# PoE.net
KiCad netlist of a schematic drawn in Altium Designer
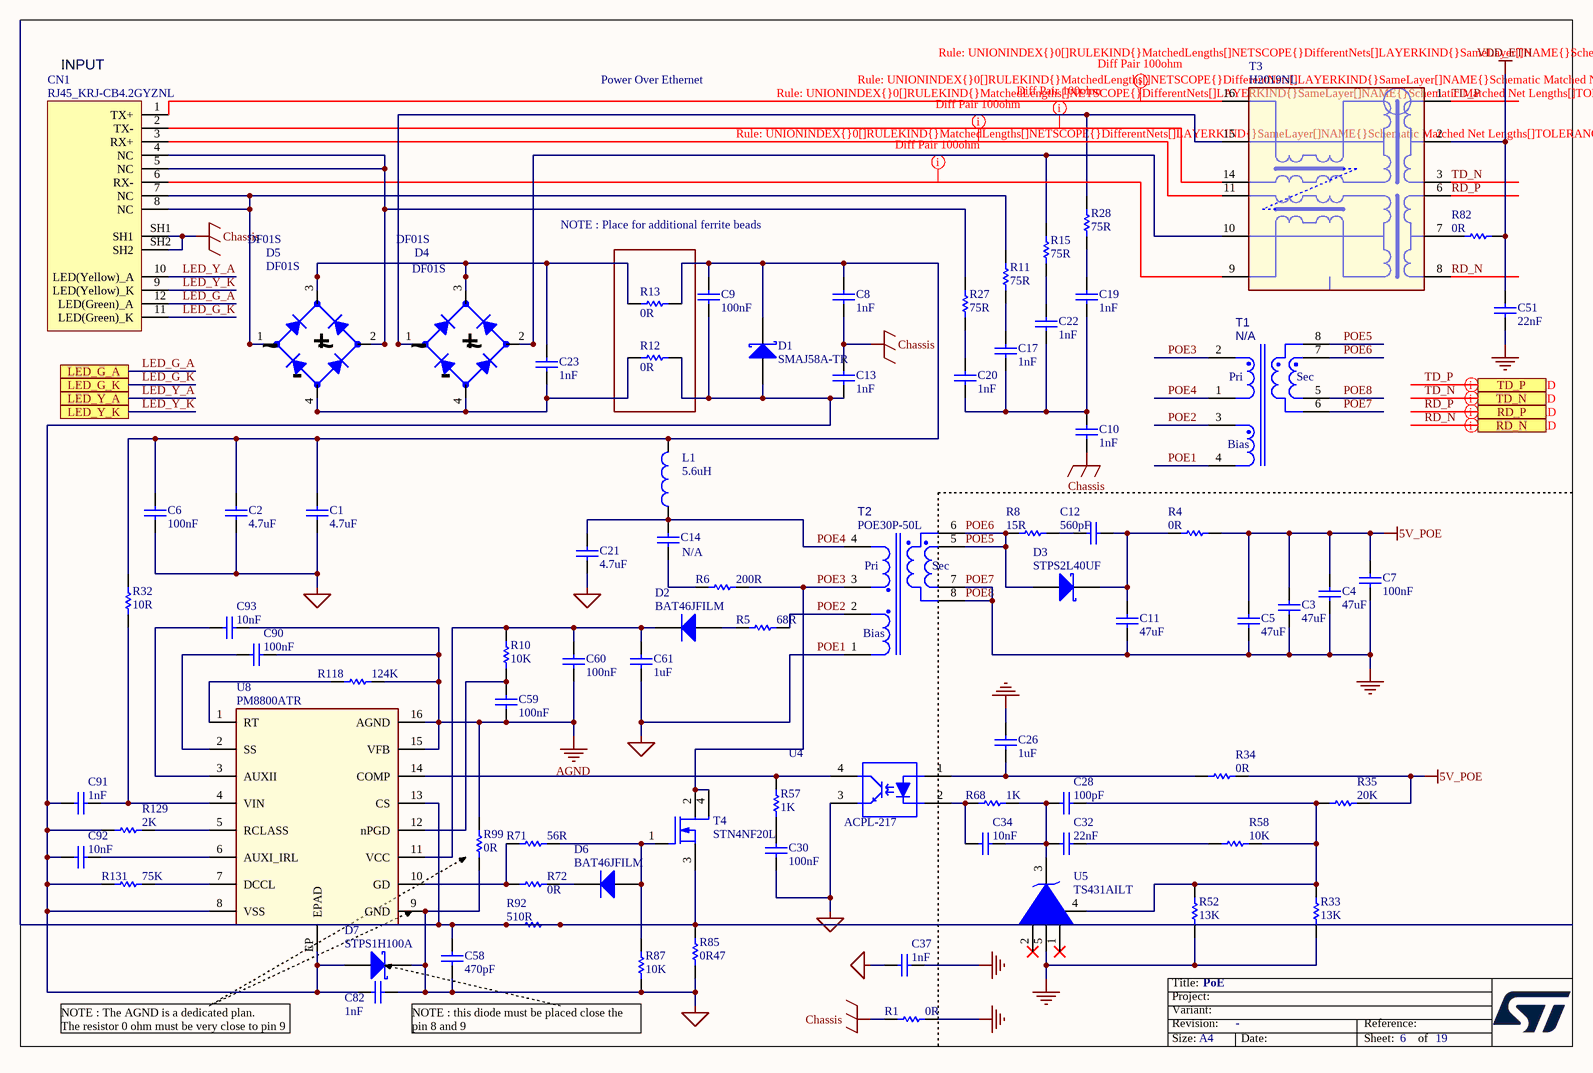
[diagram p0: PoE.SchDoc]

(export (version "E")
  (design (tool "Eeschema 10.0.6"))
  (components
    (comp (ref "C1")
      (value "4.7uF")
      (footprint "C1210")
      (description "Capacitor, MLCC, 4.7uF, 100V, X7S, +/-10%, 1210, T=2mm")
      (fields
        (field (name "INTERNAL_PART_NUMBER") "MCD-02212")
        (field (name "MANUFACTURER_PART_NUMBER") "CGA6M3X7S2A475K200AB")
      )
      (libsource (lib "MCD_PARTS_database") (part "Capacitor"))
    )
    (comp (ref "C2")
      (value "4.7uF")
      (footprint "C1210")
      (description "Capacitor, MLCC, 4.7uF, 100V, X7S, +/-10%, 1210, T=2mm")
      (fields
        (field (name "INTERNAL_PART_NUMBER") "MCD-02212")
        (field (name "MANUFACTURER_PART_NUMBER") "CGA6M3X7S2A475K200AB")
      )
      (libsource (lib "MCD_PARTS_database") (part "Capacitor"))
    )
    (comp (ref "C3")
      (value "47uF")
      (footprint "C0805")
      (description "Capacitor, MLCC, 47uF, 10V, X5R, 20%, 0805, T=1,25mm")
      (fields
        (field (name "INTERNAL_PART_NUMBER") "MCD-00204")
        (field (name "MANUFACTURER_PART_NUMBER") "GRM21BR61A476ME15K")
        (field (name "PROVIDED_BY") "Subcon")
      )
      (libsource (lib "MCD_PARTS_database") (part "Capacitor"))
    )
    (comp (ref "C4")
      (value "47uF")
      (footprint "C0805")
      (description "Capacitor, MLCC, 47uF, 10V, X5R, 20%, 0805, T=1,25mm")
      (fields
        (field (name "INTERNAL_PART_NUMBER") "MCD-00204")
        (field (name "MANUFACTURER_PART_NUMBER") "GRM21BR61A476ME15K")
        (field (name "PROVIDED_BY") "Subcon")
      )
      (libsource (lib "MCD_PARTS_database") (part "Capacitor"))
    )
    (comp (ref "C5")
      (value "47uF")
      (footprint "C0805")
      (description "Capacitor, MLCC, 47uF, 10V, X5R, 20%, 0805, T=1,25mm")
      (fields
        (field (name "INTERNAL_PART_NUMBER") "MCD-00204")
        (field (name "MANUFACTURER_PART_NUMBER") "GRM21BR61A476ME15K")
        (field (name "PROVIDED_BY") "Subcon")
      )
      (libsource (lib "MCD_PARTS_database") (part "Capacitor"))
    )
    (comp (ref "C6")
      (value "100nF")
      (footprint "C0805")
      (description "Capacitor,100nF,100V,X7R,10%,0805")
      (fields
        (field (name "INTERNAL_PART_NUMBER") "MCD-01093")
        (field (name "MANUFACTURER_PART_NUMBER") "C2012X7R2A104K125AA")
        (field (name "PROVIDED_BY") "Subcon")
      )
      (libsource (lib "MCD_PARTS_database") (part "Capacitor"))
    )
    (comp (ref "C7")
      (value "100nF")
      (footprint "C0603")
      (description "Capacitor, MLCC, 100nF, 16V, X7R, 10%, 0603, T=0,8mm")
      (fields
        (field (name "INTERNAL_PART_NUMBER") "MCD-00211")
        (field (name "MANUFACTURER_PART_NUMBER") "CC0603KRX7R7BB104")
        (field (name "PROVIDED_BY") "Subcon")
      )
      (libsource (lib "MCD_PARTS_database") (part "Capacitor"))
    )
    (comp (ref "C8")
      (value "1nF")
      (footprint "C0603")
      (description "Capacitor,1nF,100V,X7R,10%,0603")
      (fields
        (field (name "INTERNAL_PART_NUMBER") "MCD-01091")
        (field (name "MANUFACTURER_PART_NUMBER") "CC0603KRX7R0BB102")
        (field (name "PROVIDED_BY") "Subcon")
      )
      (libsource (lib "MCD_PARTS_database") (part "Capacitor"))
    )
    (comp (ref "C9")
      (value "100nF")
      (footprint "C0805")
      (description "Capacitor,100nF,100V,X7R,10%,0805")
      (fields
        (field (name "INTERNAL_PART_NUMBER") "MCD-01093")
        (field (name "MANUFACTURER_PART_NUMBER") "C2012X7R2A104K125AA")
        (field (name "PROVIDED_BY") "Subcon")
      )
      (libsource (lib "MCD_PARTS_database") (part "Capacitor"))
    )
    (comp (ref "C10")
      (value "1nF")
      (footprint "C1206_H1P6")
      (description "Capacitor, MLCC, 1nF, 2KV, X7R, 10%, 1206, T=1,25mm")
      (fields
        (field (name "INTERNAL_PART_NUMBER") "MCD-00722")
        (field (name "MANUFACTURER_PART_NUMBER") "CC1206KKX7RDBB102")
        (field (name "PROVIDED_BY") "Subcon")
      )
      (libsource (lib "MCD_PARTS_database") (part "Capacitor"))
    )
    (comp (ref "C11")
      (value "47uF")
      (footprint "C0805")
      (description "Capacitor, MLCC, 47uF, 10V, X5R, 20%, 0805, T=1,25mm")
      (fields
        (field (name "INTERNAL_PART_NUMBER") "MCD-00204")
        (field (name "MANUFACTURER_PART_NUMBER") "GRM21BR61A476ME15K")
        (field (name "PROVIDED_BY") "Subcon")
      )
      (libsource (lib "MCD_PARTS_database") (part "Capacitor"))
    )
    (comp (ref "C12")
      (value "560pF")
      (footprint "C0603")
      (description "Capacitor,560pF,16V,X7R,10%,0603")
      (fields
        (field (name "INTERNAL_PART_NUMBER") "MCD-01095")
        (field (name "MANUFACTURER_PART_NUMBER") "0603YC561KAT2A")
        (field (name "PROVIDED_BY") "Subcon")
      )
      (libsource (lib "MCD_PARTS_database") (part "Capacitor"))
    )
    (comp (ref "C13")
      (value "1nF")
      (footprint "C0603")
      (description "Capacitor,1nF,100V,X7R,10%,0603")
      (fields
        (field (name "INTERNAL_PART_NUMBER") "MCD-01091")
        (field (name "MANUFACTURER_PART_NUMBER") "CC0603KRX7R0BB102")
        (field (name "PROVIDED_BY") "Subcon")
      )
      (libsource (lib "MCD_PARTS_database") (part "Capacitor"))
    )
    (comp (ref "C14")
      (value "N/A")
      (footprint "C0603")
      (description "Capacitor,27pF,100V,NPO,5%,0603")
      (fields
        (field (name "INTERNAL_PART_NUMBER") "MCD-01096")
        (field (name "MANUFACTURER_PART_NUMBER") "CC0603JRNPO0BN270")
        (field (name "PROVIDED_BY") "Subcon")
      )
      (libsource (lib "MCD_PARTS_database") (part "Capacitor"))
    )
    (comp (ref "C17")
      (value "1nF")
      (footprint "C0603")
      (description "Capacitor,1nF,100V,X7R,10%,0603")
      (fields
        (field (name "INTERNAL_PART_NUMBER") "MCD-01091")
        (field (name "MANUFACTURER_PART_NUMBER") "CC0603KRX7R0BB102")
        (field (name "PROVIDED_BY") "Subcon")
      )
      (libsource (lib "MCD_PARTS_database") (part "Capacitor"))
    )
    (comp (ref "C19")
      (value "1nF")
      (footprint "C0603")
      (description "Capacitor,1nF,100V,X7R,10%,0603")
      (fields
        (field (name "INTERNAL_PART_NUMBER") "MCD-01091")
        (field (name "MANUFACTURER_PART_NUMBER") "CC0603KRX7R0BB102")
        (field (name "PROVIDED_BY") "Subcon")
      )
      (libsource (lib "MCD_PARTS_database") (part "Capacitor"))
    )
    (comp (ref "C20")
      (value "1nF")
      (footprint "C0603")
      (description "Capacitor,1nF,100V,X7R,10%,0603")
      (fields
        (field (name "INTERNAL_PART_NUMBER") "MCD-01091")
        (field (name "MANUFACTURER_PART_NUMBER") "CC0603KRX7R0BB102")
        (field (name "PROVIDED_BY") "Subcon")
      )
      (libsource (lib "MCD_PARTS_database") (part "Capacitor"))
    )
    (comp (ref "C21")
      (value "4.7uF")
      (footprint "C1210")
      (description "Capacitor, MLCC, 4.7uF, 100V, X7S, +/-10%, 1210, T=2mm")
      (fields
        (field (name "INTERNAL_PART_NUMBER") "MCD-02212")
        (field (name "MANUFACTURER_PART_NUMBER") "CGA6M3X7S2A475K200AB")
      )
      (libsource (lib "MCD_PARTS_database") (part "Capacitor"))
    )
    (comp (ref "C22")
      (value "1nF")
      (footprint "C0603")
      (description "Capacitor,1nF,100V,X7R,10%,0603")
      (fields
        (field (name "INTERNAL_PART_NUMBER") "MCD-01091")
        (field (name "MANUFACTURER_PART_NUMBER") "CC0603KRX7R0BB102")
        (field (name "PROVIDED_BY") "Subcon")
      )
      (libsource (lib "MCD_PARTS_database") (part "Capacitor"))
    )
    (comp (ref "C23")
      (value "1nF")
      (footprint "C0603")
      (description "Capacitor,1nF,100V,X7R,10%,0603")
      (fields
        (field (name "INTERNAL_PART_NUMBER") "MCD-01091")
        (field (name "MANUFACTURER_PART_NUMBER") "CC0603KRX7R0BB102")
        (field (name "PROVIDED_BY") "Subcon")
      )
      (libsource (lib "MCD_PARTS_database") (part "Capacitor"))
    )
    (comp (ref "C26")
      (value "1uF")
      (footprint "C0603")
      (description "Capacitor,1uF,25V,X5R,10%,0603")
      (fields
        (field (name "INTERNAL_PART_NUMBER") "MCD-01100")
        (field (name "MANUFACTURER_PART_NUMBER") "CC0603KRX5R8BB105")
        (field (name "PROVIDED_BY") "Subcon")
      )
      (libsource (lib "MCD_PARTS_database") (part "Capacitor"))
    )
    (comp (ref "C28")
      (value "100pF")
      (footprint "C0603")
      (description "Capacitor,100pF,50V,X7R,10%,0603")
      (fields
        (field (name "INTERNAL_PART_NUMBER") "MCD-01101")
        (field (name "MANUFACTURER_PART_NUMBER") "06035C101JAT4A")
        (field (name "PROVIDED_BY") "Subcon")
      )
      (libsource (lib "MCD_PARTS_database") (part "Capacitor"))
    )
    (comp (ref "C30")
      (value "100nF")
      (footprint "C0603")
      (description "Capacitor,100nF,50V,X7R,10%,0603")
      (fields
        (field (name "INTERNAL_PART_NUMBER") "MCD-01099")
        (field (name "MANUFACTURER_PART_NUMBER") "CC0603KRX7R9BB104")
        (field (name "PROVIDED_BY") "Subcon")
      )
      (libsource (lib "MCD_PARTS_database") (part "Capacitor"))
    )
    (comp (ref "C32")
      (value "22nF")
      (footprint "C0603")
      (description "Capacitor,22nF,50V,X7R,10%,0603")
      (fields
        (field (name "INTERNAL_PART_NUMBER") "MCD-01103")
        (field (name "MANUFACTURER_PART_NUMBER") "CC0603KRX7R9BB223")
        (field (name "PROVIDED_BY") "Subcon")
      )
      (libsource (lib "MCD_PARTS_database") (part "Capacitor"))
    )
    (comp (ref "C34")
      (value "10nF")
      (footprint "C0603")
      (description "Capacitor, MLCC, 10nF, 50V, X7R, +/-10%, 0603, T=0.8mm")
      (fields
        (field (name "INTERNAL_PART_NUMBER") "MCD-00017")
        (field (name "MANUFACTURER_PART_NUMBER") "CC0603KRX7R9BB103")
      )
      (libsource (lib "MCD_PARTS_database") (part "Capacitor"))
    )
    (comp (ref "C37")
      (value "1nF")
      (footprint "C1206_H1P6")
      (description "Capacitor, MLCC, 1nF, 2KV, X7R, 10%, 1206, T=1,25mm")
      (fields
        (field (name "INTERNAL_PART_NUMBER") "MCD-00722")
        (field (name "MANUFACTURER_PART_NUMBER") "CC1206KKX7RDBB102")
        (field (name "PROVIDED_BY") "Subcon")
      )
      (libsource (lib "MCD_PARTS_database") (part "Capacitor"))
    )
    (comp (ref "C51")
      (value "22nF")
      (footprint "C0603")
      (description "Capacitor,22nF,50V,X7R,10%,0603")
      (fields
        (field (name "INTERNAL_PART_NUMBER") "MCD-01103")
        (field (name "MANUFACTURER_PART_NUMBER") "CC0603KRX7R9BB223")
        (field (name "PROVIDED_BY") "Subcon")
      )
      (libsource (lib "MCD_PARTS_database") (part "Capacitor"))
    )
    (comp (ref "C58")
      (value "470pF")
      (footprint "C0603")
      (description "Capacitor,470pF,100V,X7R,10%,0603")
      (fields
        (field (name "INTERNAL_PART_NUMBER") "MCD-01104")
        (field (name "MANUFACTURER_PART_NUMBER") "06031C471KAT2A")
        (field (name "PROVIDED_BY") "Subcon")
      )
      (libsource (lib "MCD_PARTS_database") (part "Capacitor"))
    )
    (comp (ref "C59")
      (value "100nF")
      (footprint "C0603")
      (description "Capacitor,100nF,50V,X7R,10%,0603")
      (fields
        (field (name "INTERNAL_PART_NUMBER") "MCD-01099")
        (field (name "MANUFACTURER_PART_NUMBER") "CC0603KRX7R9BB104")
        (field (name "PROVIDED_BY") "Subcon")
      )
      (libsource (lib "MCD_PARTS_database") (part "Capacitor"))
    )
    (comp (ref "C60")
      (value "100nF")
      (footprint "C0603")
      (description "Capacitor,100nF,50V,X7R,10%,0603")
      (fields
        (field (name "INTERNAL_PART_NUMBER") "MCD-01099")
        (field (name "MANUFACTURER_PART_NUMBER") "CC0603KRX7R9BB104")
        (field (name "PROVIDED_BY") "Subcon")
      )
      (libsource (lib "MCD_PARTS_database") (part "Capacitor"))
    )
    (comp (ref "C61")
      (value "1uF")
      (footprint "C0603")
      (description "Capacitor,1uF,25V,X5R,10%,0603")
      (fields
        (field (name "INTERNAL_PART_NUMBER") "MCD-01100")
        (field (name "MANUFACTURER_PART_NUMBER") "CC0603KRX5R8BB105")
        (field (name "PROVIDED_BY") "Subcon")
      )
      (libsource (lib "MCD_PARTS_database") (part "Capacitor"))
    )
    (comp (ref "C82")
      (value "1nF")
      (footprint "C0603")
      (description "Capacitor,1nF,100V,X7R,10%,0603")
      (fields
        (field (name "INTERNAL_PART_NUMBER") "MCD-01091")
        (field (name "MANUFACTURER_PART_NUMBER") "CC0603KRX7R0BB102")
        (field (name "PROVIDED_BY") "Subcon")
      )
      (libsource (lib "MCD_PARTS_database") (part "Capacitor"))
    )
    (comp (ref "C90")
      (value "100nF")
      (footprint "C0603")
      (description "Capacitor,100nF,50V,X7R,10%,0603")
      (fields
        (field (name "INTERNAL_PART_NUMBER") "MCD-01099")
        (field (name "MANUFACTURER_PART_NUMBER") "CC0603KRX7R9BB104")
        (field (name "PROVIDED_BY") "Subcon")
      )
      (libsource (lib "MCD_PARTS_database") (part "Capacitor"))
    )
    (comp (ref "C91")
      (value "1nF")
      (footprint "C0603")
      (description "Capacitor,1nF,100V,X7R,10%,0603")
      (fields
        (field (name "INTERNAL_PART_NUMBER") "MCD-01091")
        (field (name "MANUFACTURER_PART_NUMBER") "CC0603KRX7R0BB102")
        (field (name "PROVIDED_BY") "Subcon")
      )
      (libsource (lib "MCD_PARTS_database") (part "Capacitor"))
    )
    (comp (ref "C92")
      (value "10nF")
      (footprint "C0603")
      (description "Capacitor,10nF,100V,X7R,10%,0603")
      (fields
        (field (name "INTERNAL_PART_NUMBER") "MCD-01098")
        (field (name "MANUFACTURER_PART_NUMBER") "CC0603KRX7R0BB103")
        (field (name "PROVIDED_BY") "Subcon")
      )
      (libsource (lib "MCD_PARTS_database") (part "Capacitor"))
    )
    (comp (ref "C93")
      (value "10nF")
      (footprint "C0603")
      (description "Capacitor,10nF,100V,X7R,10%,0603")
      (fields
        (field (name "INTERNAL_PART_NUMBER") "MCD-01098")
        (field (name "MANUFACTURER_PART_NUMBER") "CC0603KRX7R0BB103")
        (field (name "PROVIDED_BY") "Subcon")
      )
      (libsource (lib "MCD_PARTS_database") (part "Capacitor"))
    )
    (comp (ref "CN1")
      (value "RJ45_KRJ-CB4.2GYZNL")
      (footprint "CON_RJ45_DGKYD_KRJ-CB4.2GYZNL")
      (description "RJ45 jack, single port, with LEDS, Metal shielded dip low profile")
      (fields
        (field (name "INTERNAL_PART_NUMBER") "MCD-00717")
        (field (name "MANUFACTURER_PART_NUMBER") "KRJ-CB4.2GYZNL")
        (field (name "PROVIDED_BY") "Subcon")
      )
      (libsource (lib "MCD_PARTS_database") (part "RJ45_KRJ-CB4.2GYZNL"))
    )
    (comp (ref "D1")
      (value "SMAJ58A-TR")
      (footprint "DIO_SMA_1A_2K")
      (description "Transil 400W, VRM=58V")
      (fields
        (field (name "INTERNAL_PART_NUMBER") "MCD-01083")
        (field (name "MANUFACTURER") "STMICROELECTRONICS")
        (field (name "PROVIDED_BY") "Subcon")
      )
      (libsource (lib "MCD_PARTS_database") (part "SMAJ58A-TR"))
    )
    (comp (ref "D2")
      (value "BAT46JFILM")
      (footprint "DIO_SOD323_1A_2K")
      (description "Schottky Single diode,150mA, 100V")
      (fields
        (field (name "INTERNAL_PART_NUMBER") "MCD-01064")
        (field (name "MANUFACTURER") "STMICROELECTRONICS")
        (field (name "PROVIDED_BY") "Subcon")
      )
      (libsource (lib "MCD_PARTS_database") (part "DIODE"))
    )
    (comp (ref "D3")
      (value "STPS2L40UF")
      (footprint "DIO_SMB-FLAT_1A_2K")
      (description "Low drop power Schottky rectifier(2A, 40V, 0.34V)")
      (fields
        (field (name "INTERNAL_PART_NUMBER") "MCD-01087")
        (field (name "MANUFACTURER") "STMICROELECTRONICS")
        (field (name "PROVIDED_BY") "Subcon")
      )
      (libsource (lib "MCD_PARTS_database") (part "STPS2L40UF"))
    )
    (comp (ref "D4")
      (value "DF01S")
      (footprint "BRF_VISHAY_DFS_DF01S")
      (description "IC, Bridge Rectifiers, Miniature Glass Passivated Single-Phase, Surface Mount")
      (fields
        (field (name "INTERNAL_PART_NUMBER") "MCD-01065")
        (field (name "MANUFACTURER") "VISHAY")
        (field (name "ALTIUM_VALUE") "DF01S")
      )
      (libsource (lib "MCD_PARTS_database") (part "DF01S"))
    )
    (comp (ref "D5")
      (value "DF01S")
      (footprint "BRF_VISHAY_DFS_DF01S")
      (description "IC, Bridge Rectifiers, Miniature Glass Passivated Single-Phase, Surface Mount")
      (fields
        (field (name "INTERNAL_PART_NUMBER") "MCD-01065")
        (field (name "MANUFACTURER") "VISHAY")
        (field (name "ALTIUM_VALUE") "DF01S")
      )
      (libsource (lib "MCD_PARTS_database") (part "DF01S"))
    )
    (comp (ref "D6")
      (value "BAT46JFILM")
      (footprint "DIO_SOD323_1A_2K")
      (description "Schottky Single diode,150mA, 100V")
      (fields
        (field (name "INTERNAL_PART_NUMBER") "MCD-01064")
        (field (name "MANUFACTURER") "STMICROELECTRONICS")
        (field (name "PROVIDED_BY") "Subcon")
      )
      (libsource (lib "MCD_PARTS_database") (part "DIODE"))
    )
    (comp (ref "D7")
      (value "STPS1H100A")
      (footprint "DIO_SMA_DO214-AC_1A_2K")
      (description "High voltage power Schottky rectifier")
      (fields
        (field (name "INTERNAL_PART_NUMBER") "MCD-01165")
        (field (name "MANUFACTURER") "STMICROELECTRONICS")
        (field (name "PROVIDED_BY") "Subcon")
      )
      (libsource (lib "MCD_PARTS_database") (part "SMAJ58A-TR"))
    )
    (comp (ref "L1")
      (value "5.6uH")
      (footprint "IND_POWER_COILCRAFT_ME3220")
      (description "Power Inductor, 5.6uH, 0.2R, ME3220-562ML")
      (fields
        (field (name "INTERNAL_PART_NUMBER") "MCD-01109")
        (field (name "MANUFACTURER_PART_NUMBER") "ME3220-562ML")
        (field (name "PROVIDED_BY") "Subcon")
      )
      (libsource (lib "MCD_PARTS_database") (part "Inductor"))
    )
    (comp (ref "R1")
      (value "0R")
      (footprint "R0805")
      (description "Resistor,0R,0805,5%")
      (fields
        (field (name "INTERNAL_PART_NUMBER") "MCD-00179")
        (field (name "MANUFACTURER_PART_NUMBER") "RC0805JR-070RL")
        (field (name "PROVIDED_BY") "Subcon")
      )
      (libsource (lib "MCD_PARTS_database") (part "Resistor"))
    )
    (comp (ref "R4")
      (value "0R")
      (footprint "R0603")
      (description "Resistor,0R,0603,5%,1/10W")
      (fields
        (field (name "INTERNAL_PART_NUMBER") "MCD-00056")
        (field (name "MANUFACTURER_PART_NUMBER") "RC0603JR-070RL")
        (field (name "PROVIDED_BY") "subcon")
      )
      (libsource (lib "MCD_PARTS_database") (part "Resistor"))
    )
    (comp (ref "R5")
      (value "68R")
      (footprint "R0805")
      (description "Resistor,68R,0805,1%")
      (fields
        (field (name "INTERNAL_PART_NUMBER") "MCD-01115")
        (field (name "MANUFACTURER_PART_NUMBER") "RC0805FR-0768RL")
        (field (name "PROVIDED_BY") "Subcon")
      )
      (libsource (lib "MCD_PARTS_database") (part "Resistor"))
    )
    (comp (ref "R6")
      (value "200R")
      (footprint "R1206_H0P55")
      (description "Resistor,200R,1206,1%")
      (fields
        (field (name "INTERNAL_PART_NUMBER") "MCD-01114")
        (field (name "MANUFACTURER_PART_NUMBER") "LTR18EZPF2000")
        (field (name "PROVIDED_BY") "Subcon")
      )
      (libsource (lib "MCD_PARTS_database") (part "Resistor"))
    )
    (comp (ref "R8")
      (value "15R")
      (footprint "R0805")
      (description "Resistor,15R,0805,1%")
      (fields
        (field (name "INTERNAL_PART_NUMBER") "MCD-01113")
        (field (name "MANUFACTURER_PART_NUMBER") "RC0805FR-0715RL")
        (field (name "PROVIDED_BY") "Subcon")
      )
      (libsource (lib "MCD_PARTS_database") (part "Resistor"))
    )
    (comp (ref "R10")
      (value "10K")
      (footprint "R0603")
      (description "Resistor,10K,0603,1%,1/10W")
      (fields
        (field (name "INTERNAL_PART_NUMBER") "MCD-00220")
        (field (name "MANUFACTURER_PART_NUMBER") "RC0603FR-0710KL")
        (field (name "PROVIDED_BY") "Subcon")
      )
      (libsource (lib "MCD_PARTS_database") (part "Resistor"))
    )
    (comp (ref "R11")
      (value "75R")
      (footprint "R0805")
      (description "Resistor,75R,0805,1%")
      (fields
        (field (name "INTERNAL_PART_NUMBER") "MCD-01112")
        (field (name "MANUFACTURER_PART_NUMBER") "RC0805FR-0775RL")
        (field (name "PROVIDED_BY") "Subcon")
      )
      (libsource (lib "MCD_PARTS_database") (part "Resistor"))
    )
    (comp (ref "R12")
      (value "0R")
      (footprint "R0805")
      (description "Resistor,0R,0805,5%")
      (fields
        (field (name "INTERNAL_PART_NUMBER") "MCD-00179")
        (field (name "MANUFACTURER_PART_NUMBER") "RC0805JR-070RL")
        (field (name "PROVIDED_BY") "Subcon")
      )
      (libsource (lib "MCD_PARTS_database") (part "Resistor"))
    )
    (comp (ref "R13")
      (value "0R")
      (footprint "R0805")
      (description "Resistor,0R,0805,5%")
      (fields
        (field (name "INTERNAL_PART_NUMBER") "MCD-00179")
        (field (name "MANUFACTURER_PART_NUMBER") "RC0805JR-070RL")
        (field (name "PROVIDED_BY") "Subcon")
      )
      (libsource (lib "MCD_PARTS_database") (part "Resistor"))
    )
    (comp (ref "R15")
      (value "75R")
      (footprint "R0805")
      (description "Resistor,75R,0805,1%")
      (fields
        (field (name "INTERNAL_PART_NUMBER") "MCD-01112")
        (field (name "MANUFACTURER_PART_NUMBER") "RC0805FR-0775RL")
        (field (name "PROVIDED_BY") "Subcon")
      )
      (libsource (lib "MCD_PARTS_database") (part "Resistor"))
    )
    (comp (ref "R27")
      (value "75R")
      (footprint "R0805")
      (description "Resistor,75R,0805,1%")
      (fields
        (field (name "INTERNAL_PART_NUMBER") "MCD-01112")
        (field (name "MANUFACTURER_PART_NUMBER") "RC0805FR-0775RL")
        (field (name "PROVIDED_BY") "Subcon")
      )
      (libsource (lib "MCD_PARTS_database") (part "Resistor"))
    )
    (comp (ref "R28")
      (value "75R")
      (footprint "R0805")
      (description "Resistor,75R,0805,1%")
      (fields
        (field (name "INTERNAL_PART_NUMBER") "MCD-01112")
        (field (name "MANUFACTURER_PART_NUMBER") "RC0805FR-0775RL")
        (field (name "PROVIDED_BY") "Subcon")
      )
      (libsource (lib "MCD_PARTS_database") (part "Resistor"))
    )
    (comp (ref "R32")
      (value "10R")
      (footprint "R0805")
      (description "Resistor,10R,0805,1%,Stackpole,1/4W")
      (fields
        (field (name "INTERNAL_PART_NUMBER") "MCD-01111")
        (field (name "MANUFACTURER_PART_NUMBER") "RNCP0805FTD10R0")
        (field (name "PROVIDED_BY") "Subcon")
      )
      (libsource (lib "MCD_PARTS_database") (part "Resistor"))
    )
    (comp (ref "R33")
      (value "13K")
      (footprint "R0603")
      (description "Resistor,13K,0603,1%,1/10W")
      (fields
        (field (name "INTERNAL_PART_NUMBER") "MCD-00384")
        (field (name "MANUFACTURER_PART_NUMBER") "RC0603FR-0713KL")
        (field (name "PROVIDED_BY") "Subcon")
      )
      (libsource (lib "MCD_PARTS_database") (part "Resistor"))
    )
    (comp (ref "R34")
      (value "0R")
      (footprint "R0805")
      (description "Resistor,0R,0805,5%")
      (fields
        (field (name "INTERNAL_PART_NUMBER") "MCD-00179")
        (field (name "MANUFACTURER_PART_NUMBER") "RC0805JR-070RL")
        (field (name "PROVIDED_BY") "Subcon")
      )
      (libsource (lib "MCD_PARTS_database") (part "Resistor"))
    )
    (comp (ref "R35")
      (value "20K")
      (footprint "R0603")
      (description "Resistor,20K,0603,1%,1/10W")
      (fields
        (field (name "INTERNAL_PART_NUMBER") "MCD-00422")
        (field (name "MANUFACTURER_PART_NUMBER") "RC0603FR-0720KL")
        (field (name "PROVIDED_BY") "Subcon")
      )
      (libsource (lib "MCD_PARTS_database") (part "Resistor"))
    )
    (comp (ref "R52")
      (value "13K")
      (footprint "R0603")
      (description "Resistor,13K,0603,1%,1/10W")
      (fields
        (field (name "INTERNAL_PART_NUMBER") "MCD-00384")
        (field (name "MANUFACTURER_PART_NUMBER") "RC0603FR-0713KL")
        (field (name "PROVIDED_BY") "Subcon")
      )
      (libsource (lib "MCD_PARTS_database") (part "Resistor"))
    )
    (comp (ref "R57")
      (value "1K")
      (footprint "R0603")
      (description "Resistor,1K,0603,1%,1/10W")
      (fields
        (field (name "INTERNAL_PART_NUMBER") "MCD-00070")
        (field (name "MANUFACTURER_PART_NUMBER") "RC0603FR-071KL")
        (field (name "PROVIDED_BY") "Subcon")
      )
      (libsource (lib "MCD_PARTS_database") (part "Resistor"))
    )
    (comp (ref "R58")
      (value "10K")
      (footprint "R0603")
      (description "Resistor,10K,0603,1%,1/10W")
      (fields
        (field (name "INTERNAL_PART_NUMBER") "MCD-00220")
        (field (name "MANUFACTURER_PART_NUMBER") "RC0603FR-0710KL")
        (field (name "PROVIDED_BY") "Subcon")
      )
      (libsource (lib "MCD_PARTS_database") (part "Resistor"))
    )
    (comp (ref "R68")
      (value "1K")
      (footprint "R0603")
      (description "Resistor,1K,0603,1%,1/10W")
      (fields
        (field (name "INTERNAL_PART_NUMBER") "MCD-00070")
        (field (name "MANUFACTURER_PART_NUMBER") "RC0603FR-071KL")
        (field (name "PROVIDED_BY") "Subcon")
      )
      (libsource (lib "MCD_PARTS_database") (part "Resistor"))
    )
    (comp (ref "R71")
      (value "56R")
      (footprint "R0805")
      (description "Resistor,56R,0805,1%")
      (fields
        (field (name "INTERNAL_PART_NUMBER") "MCD-01118")
        (field (name "MANUFACTURER_PART_NUMBER") "RC0805FR-0756RL")
        (field (name "PROVIDED_BY") "Subcon")
      )
      (libsource (lib "MCD_PARTS_database") (part "Resistor"))
    )
    (comp (ref "R72")
      (value "0R")
      (footprint "R0805")
      (description "Resistor,0R,0805,5%")
      (fields
        (field (name "INTERNAL_PART_NUMBER") "MCD-00179")
        (field (name "MANUFACTURER_PART_NUMBER") "RC0805JR-070RL")
        (field (name "PROVIDED_BY") "Subcon")
      )
      (libsource (lib "MCD_PARTS_database") (part "Resistor"))
    )
    (comp (ref "R82")
      (value "0R")
      (footprint "R0805")
      (description "Resistor,0R,0805,5%")
      (fields
        (field (name "INTERNAL_PART_NUMBER") "MCD-00179")
        (field (name "MANUFACTURER_PART_NUMBER") "RC0805JR-070RL")
        (field (name "PROVIDED_BY") "Subcon")
      )
      (libsource (lib "MCD_PARTS_database") (part "Resistor"))
    )
    (comp (ref "R85")
      (value "0R47")
      (footprint "R1206_H0P55")
      (description "Resistor,0.47R,1206,1%")
      (fields
        (field (name "INTERNAL_PART_NUMBER") "MCD-01119")
        (field (name "MANUFACTURER_PART_NUMBER") "RL1206FR-070R47L")
        (field (name "PROVIDED_BY") "Subcon")
      )
      (libsource (lib "MCD_PARTS_database") (part "Resistor"))
    )
    (comp (ref "R87")
      (value "10K")
      (footprint "R0603")
      (description "Resistor,10K,0603,1%,1/10W")
      (fields
        (field (name "INTERNAL_PART_NUMBER") "MCD-00220")
        (field (name "MANUFACTURER_PART_NUMBER") "RC0603FR-0710KL")
        (field (name "PROVIDED_BY") "Subcon")
      )
      (libsource (lib "MCD_PARTS_database") (part "Resistor"))
    )
    (comp (ref "R92")
      (value "510R")
      (footprint "R0603")
      (description "Resistor,510R,0603,1%,1/10W")
      (fields
        (field (name "INTERNAL_PART_NUMBER") "MCD-00225")
        (field (name "MANUFACTURER_PART_NUMBER") "RC0603FR-07510RL")
        (field (name "PROVIDED_BY") "Subcon")
      )
      (libsource (lib "MCD_PARTS_database") (part "Resistor"))
    )
    (comp (ref "R99")
      (value "0R")
      (footprint "R0603")
      (description "Resistor,0R,0603,5%,1/10W")
      (fields
        (field (name "INTERNAL_PART_NUMBER") "MCD-00056")
        (field (name "MANUFACTURER_PART_NUMBER") "RC0603JR-070RL")
        (field (name "PROVIDED_BY") "subcon")
      )
      (libsource (lib "MCD_PARTS_database") (part "Resistor"))
    )
    (comp (ref "R118")
      (value "124K")
      (footprint "R0603")
      (description "Resistor,124K,0603,1%")
      (fields
        (field (name "INTERNAL_PART_NUMBER") "MCD-01116")
        (field (name "MANUFACTURER_PART_NUMBER") "RC0603FR-07124KL")
        (field (name "PROVIDED_BY") "Subcon")
      )
      (libsource (lib "MCD_PARTS_database") (part "Resistor"))
    )
    (comp (ref "R129")
      (value "2K")
      (footprint "R0805")
      (description "Resistor,2K,0805,1%")
      (fields
        (field (name "INTERNAL_PART_NUMBER") "MCD-01117")
        (field (name "MANUFACTURER_PART_NUMBER") "RC0805FR-072KL")
        (field (name "PROVIDED_BY") "Subcon")
      )
      (libsource (lib "MCD_PARTS_database") (part "Resistor"))
    )
    (comp (ref "R131")
      (value "75K")
      (footprint "R0603")
      (description "Resistor,75K,0603,1%,1/10W")
      (fields
        (field (name "INTERNAL_PART_NUMBER") "MCD-00522")
        (field (name "MANUFACTURER_PART_NUMBER") "RC0603FR-0775KL")
        (field (name "PROVIDED_BY") "Subcon")
      )
      (libsource (lib "MCD_PARTS_database") (part "Resistor"))
    )
    (comp (ref "T1")
      (value "N/A")
      (footprint "TRS_WURTH_750315923")
      (description "Flyback Transformers for 3 Watt, PoE applications")
      (fields
        (field (name "INTERNAL_PART_NUMBER") "MCD-01063")
        (field (name "MANUFACTURER_PART_NUMBER") "750315923")
        (field (name "PROVIDED_BY") "Subcon")
      )
      (libsource (lib "MCD_PARTS_database") (part "TRS_750315923"))
    )
    (comp (ref "T2")
      (value "POE30P-50L")
      (footprint "TRS_COILCRAFT_POE30P-50L")
      (description "Flyback Transformers for 3 Watt, PoE applications, CoilCraft Cyntec")
      (fields
        (field (name "INTERNAL_PART_NUMBER") "MCD-01081")
        (field (name "MANUFACTURER") "COILCRAFT")
        (field (name "PROVIDED_BY") "Subcon")
      )
      (libsource (lib "MCD_PARTS_database") (part "POE30P-50L"))
    )
    (comp (ref "T3")
      (value "H2019NL")
      (footprint "TRS_PULSE_H2019NL")
      (description "10/100BASE-TX VoIP Magnetics Modules, Data Transformer")
      (fields
        (field (name "INTERNAL_PART_NUMBER") "MCD-01067")
        (field (name "MANUFACTURER") "PULSE ELECTRONICS")
        (field (name "PROVIDED_BY") "Subcon")
      )
      (libsource (lib "MCD_PARTS_database") (part "H2019NL"))
    )
    (comp (ref "T4")
      (value "STN4NF20L")
      (footprint "MOS_SOT223-TAB")
      (description "Annel 200 V, 1.1ohm, 1 A, low gate charge STripFET II, Power MOSFET")
      (fields
        (field (name "INTERNAL_PART_NUMBER") "MCD-01086")
        (field (name "MANUFACTURER") "STMICROELECTRONICS")
        (field (name "PROVIDED_BY") "Subcon")
      )
      (libsource (lib "MCD_PARTS_database") (part "STN4NF20L"))
    )
    (comp (ref "U4")
      (value "ACPL-217")
      (footprint "OPT_MINI-FLAT_FAIRCHILD_HMHA2801A")
      (description "IC, Half-Pitch Phototransistor Optocoupler, DC Input, 3750V, SO-4")
      (fields
        (field (name "INTERNAL_PART_NUMBER") "MCD-03054")
        (field (name "MANUFACTURER") "BROADCOM LIMITED")
      )
      (libsource (lib "MCD_PARTS_database") (part "HMHA2801A"))
    )
    (comp (ref "U5")
      (value "TS431AILT")
      (footprint "MOS_SOT23-5L")
      (description "Low voltage adjustable shunt reference")
      (fields
        (field (name "INTERNAL_PART_NUMBER") "MCD-01089")
        (field (name "MANUFACTURER") "STMICROELECTRONICS")
        (field (name "PROVIDED_BY") "Subcon")
      )
      (libsource (lib "MCD_PARTS_database") (part "TS431AILT"))
    )
    (comp (ref "U8")
      (value "PM8800ATR")
      (footprint "ICC_HTSSOP16-EPAD_5X4P4_P065")
      (fields
        (field (name "INTERNAL_PART_NUMBER") "MCD-01080")
        (field (name "MANUFACTURER") "STMICROELECTRONICS")
        (field (name "BMS_PART_NUMBER") "9177966")
        (field (name "PROVIDED_BY") "Subcon")
      )
      (libsource (lib "MCD_PARTS_database") (part "PM8800ATR"))
    )
  )
  (nets
    (net (code "1") (name "/LED_G_A") (class "Default")
      (node (ref "CN1") (pin "12") (pinfunction "LED(Green)_A_12") (pintype "passive"))
    )
    (net (code "2") (name "/LED_G_K") (class "Default")
      (node (ref "CN1") (pin "11") (pinfunction "LED(Green)_K_11") (pintype "passive"))
    )
    (net (code "3") (name "/LED_Y_A") (class "Default")
      (node (ref "CN1") (pin "10") (pinfunction "LED(Yellow)_A_10") (pintype "passive"))
    )
    (net (code "4") (name "/LED_Y_K") (class "Default")
      (node (ref "CN1") (pin "9") (pinfunction "LED(Yellow)_K_9") (pintype "passive"))
    )
    (net (code "5") (name "/POE2") (class "Default")
      (node (ref "R5") (pin "2") (pinfunction "2_2") (pintype "passive"))
      (node (ref "T1") (pin "3") (pinfunction "3_3") (pintype "passive"))
      (node (ref "T2") (pin "2") (pinfunction "2_2") (pintype "passive"))
    )
    (net (code "6") (name "/POE3") (class "Default")
      (node (ref "R6") (pin "2") (pinfunction "2_2") (pintype "passive"))
      (node (ref "T1") (pin "2") (pinfunction "2_2") (pintype "passive"))
      (node (ref "T2") (pin "3") (pinfunction "3_3") (pintype "passive"))
      (node (ref "T4") (pin "2") (pinfunction "D_2") (pintype "passive"))
      (node (ref "T4") (pin "4") (pinfunction "D_4") (pintype "passive"))
    )
    (net (code "7") (name "/POE4") (class "Default")
      (node (ref "C14") (pin "2") (pinfunction "2_2") (pintype "passive"))
      (node (ref "C21") (pin "2") (pinfunction "2_2") (pintype "passive"))
      (node (ref "L1") (pin "1") (pinfunction "1_1") (pintype "passive"))
      (node (ref "T1") (pin "1") (pinfunction "1_1") (pintype "passive"))
      (node (ref "T2") (pin "4") (pinfunction "4_4") (pintype "passive"))
    )
    (net (code "8") (name "/POE5") (class "Default")
      (node (ref "D3") (pin "1") (pinfunction "A_1") (pintype "passive"))
      (node (ref "R8") (pin "1") (pinfunction "1_1") (pintype "passive"))
      (node (ref "T1") (pin "7") (pinfunction "7_7") (pintype "passive"))
      (node (ref "T1") (pin "8") (pinfunction "8_8") (pintype "passive"))
      (node (ref "T2") (pin "5") (pinfunction "5_5") (pintype "passive"))
      (node (ref "T2") (pin "6") (pinfunction "6_6") (pintype "passive"))
    )
    (net (code "9") (name "/RD_N") (class "Default")
      (node (ref "T3") (pin "8") (pinfunction "rd-_8") (pintype "passive"))
    )
    (net (code "10") (name "/RD_P") (class "Default")
      (node (ref "T3") (pin "6") (pinfunction "rd+_6") (pintype "passive"))
    )
    (net (code "11") (name "/TD_N") (class "Default")
      (node (ref "T3") (pin "3") (pinfunction "td-_3") (pintype "passive"))
    )
    (net (code "12") (name "/TD_P") (class "Default")
      (node (ref "T3") (pin "1") (pinfunction "td+_1") (pintype "passive"))
    )
    (net (code "13") (name "5V_POE") (class "Default")
      (node (ref "C3") (pin "2") (pinfunction "2_2") (pintype "passive"))
      (node (ref "C4") (pin "2") (pinfunction "2_2") (pintype "passive"))
      (node (ref "C5") (pin "2") (pinfunction "2_2") (pintype "passive"))
      (node (ref "C7") (pin "2") (pinfunction "2_2") (pintype "passive"))
      (node (ref "R34") (pin "2") (pinfunction "2_2") (pintype "passive"))
      (node (ref "R35") (pin "2") (pinfunction "2_2") (pintype "passive"))
      (node (ref "R4") (pin "2") (pinfunction "2_2") (pintype "passive"))
    )
    (net (code "14") (name "AGND") (class "Default")
      (node (ref "C59") (pin "1") (pinfunction "1_1") (pintype "passive"))
      (node (ref "C60") (pin "1") (pinfunction "1_1") (pintype "passive"))
      (node (ref "C90") (pin "2") (pinfunction "2_2") (pintype "passive"))
      (node (ref "C93") (pin "2") (pinfunction "2_2") (pintype "passive"))
      (node (ref "R118") (pin "2") (pinfunction "2_2") (pintype "passive"))
      (node (ref "R99") (pin "2") (pinfunction "2_2") (pintype "passive"))
      (node (ref "U8") (pin "15") (pinfunction "VFB_15") (pintype "passive"))
      (node (ref "U8") (pin "16") (pinfunction "AGND_16") (pintype "passive"))
    )
    (net (code "15") (name "Chassis") (class "Default")
      (node (ref "C10") (pin "1") (pinfunction "1_1") (pintype "passive"))
      (node (ref "C13") (pin "2") (pinfunction "2_2") (pintype "passive"))
      (node (ref "C8") (pin "1") (pinfunction "1_1") (pintype "passive"))
      (node (ref "CN1") (pin "SH1") (pinfunction "SH1_SH1") (pintype "passive"))
      (node (ref "CN1") (pin "SH2") (pinfunction "SH2_SH2") (pintype "passive"))
      (node (ref "R1") (pin "1") (pinfunction "1_1") (pintype "passive"))
    )
    (net (code "16") (name "GND") (class "Default")
      (node (ref "C11") (pin "1") (pinfunction "1_1") (pintype "passive"))
      (node (ref "C26") (pin "2") (pinfunction "2_2") (pintype "passive"))
      (node (ref "C3") (pin "1") (pinfunction "1_1") (pintype "passive"))
      (node (ref "C37") (pin "2") (pinfunction "2_2") (pintype "passive"))
      (node (ref "C4") (pin "1") (pinfunction "1_1") (pintype "passive"))
      (node (ref "C5") (pin "1") (pinfunction "1_1") (pintype "passive"))
      (node (ref "C51") (pin "1") (pinfunction "1_1") (pintype "passive"))
      (node (ref "C7") (pin "1") (pinfunction "1_1") (pintype "passive"))
      (node (ref "R1") (pin "2") (pinfunction "2_2") (pintype "passive"))
      (node (ref "R33") (pin "2") (pinfunction "2_2") (pintype "passive"))
      (node (ref "R52") (pin "1") (pinfunction "1_1") (pintype "passive"))
      (node (ref "T1") (pin "5") (pinfunction "5_5") (pintype "passive"))
      (node (ref "T1") (pin "6") (pinfunction "6_6") (pintype "passive"))
      (node (ref "T2") (pin "7") (pinfunction "7_7") (pintype "passive"))
      (node (ref "T2") (pin "8") (pinfunction "8_8") (pintype "passive"))
      (node (ref "U5") (pin "5") (pinfunction "A_5") (pintype "passive"))
    )
    (net (code "17") (name "GND_POWER_IN") (class "Default")
      (node (ref "C1") (pin "1") (pinfunction "1_1") (pintype "passive"))
      (node (ref "C2") (pin "1") (pinfunction "1_1") (pintype "passive"))
      (node (ref "C21") (pin "1") (pinfunction "1_1") (pintype "passive"))
      (node (ref "C30") (pin "1") (pinfunction "1_1") (pintype "passive"))
      (node (ref "C37") (pin "1") (pinfunction "1_1") (pintype "passive"))
      (node (ref "C58") (pin "1") (pinfunction "1_1") (pintype "passive"))
      (node (ref "C6") (pin "1") (pinfunction "1_1") (pintype "passive"))
      (node (ref "C61") (pin "1") (pinfunction "1_1") (pintype "passive"))
      (node (ref "C82") (pin "1") (pinfunction "1_1") (pintype "passive"))
      (node (ref "D7") (pin "2") (pinfunction "K_2") (pintype "passive"))
      (node (ref "R85") (pin "1") (pinfunction "1_1") (pintype "passive"))
      (node (ref "R87") (pin "1") (pinfunction "1_1") (pintype "passive"))
      (node (ref "R99") (pin "1") (pinfunction "1_1") (pintype "passive"))
      (node (ref "T1") (pin "4") (pinfunction "4_4") (pintype "passive"))
      (node (ref "T2") (pin "1") (pinfunction "1_1") (pintype "passive"))
      (node (ref "U4") (pin "3") (pinfunction "Emitter_3") (pintype "passive"))
      (node (ref "U8") (pin "9") (pinfunction "GND_9") (pintype "passive"))
    )
    (net (code "18") (name "Net-(C10-Pad2)") (class "Default")
      (node (ref "C10") (pin "2") (pinfunction "2_2") (pintype "passive"))
      (node (ref "C17") (pin "1") (pinfunction "1_1") (pintype "passive"))
      (node (ref "C19") (pin "1") (pinfunction "1_1") (pintype "passive"))
      (node (ref "C20") (pin "1") (pinfunction "1_1") (pintype "passive"))
      (node (ref "C22") (pin "1") (pinfunction "1_1") (pintype "passive"))
    )
    (net (code "19") (name "Net-(C12-Pad1)") (class "Default")
      (node (ref "C12") (pin "1") (pinfunction "1_1") (pintype "passive"))
      (node (ref "R8") (pin "2") (pinfunction "2_2") (pintype "passive"))
    )
    (net (code "20") (name "Net-(C14-Pad1)") (class "Default")
      (node (ref "C14") (pin "1") (pinfunction "1_1") (pintype "passive"))
      (node (ref "R6") (pin "1") (pinfunction "1_1") (pintype "passive"))
    )
    (net (code "21") (name "Net-(C17-Pad2)") (class "Default")
      (node (ref "C17") (pin "2") (pinfunction "2_2") (pintype "passive"))
      (node (ref "R11") (pin "1") (pinfunction "1_1") (pintype "passive"))
    )
    (net (code "22") (name "Net-(C19-Pad2)") (class "Default")
      (node (ref "C19") (pin "2") (pinfunction "2_2") (pintype "passive"))
      (node (ref "R28") (pin "1") (pinfunction "1_1") (pintype "passive"))
    )
    (net (code "23") (name "Net-(C20-Pad2)") (class "Default")
      (node (ref "C20") (pin "2") (pinfunction "2_2") (pintype "passive"))
      (node (ref "R27") (pin "1") (pinfunction "1_1") (pintype "passive"))
    )
    (net (code "24") (name "Net-(C22-Pad2)") (class "Default")
      (node (ref "C22") (pin "2") (pinfunction "2_2") (pintype "passive"))
      (node (ref "R15") (pin "1") (pinfunction "1_1") (pintype "passive"))
    )
    (net (code "25") (name "Net-(C30-Pad2)") (class "Default")
      (node (ref "C30") (pin "2") (pinfunction "2_2") (pintype "passive"))
      (node (ref "R57") (pin "1") (pinfunction "1_1") (pintype "passive"))
    )
    (net (code "26") (name "Net-(C32-Pad2)") (class "Default")
      (node (ref "C32") (pin "2") (pinfunction "2_2") (pintype "passive"))
      (node (ref "R58") (pin "2") (pinfunction "2_2") (pintype "passive"))
    )
    (net (code "27") (name "Net-(CN1-RX+)") (class "Default")
      (node (ref "CN1") (pin "3") (pinfunction "RX+_3") (pintype "passive"))
      (node (ref "T3") (pin "11") (pinfunction "rx1+_11") (pintype "passive"))
    )
    (net (code "28") (name "Net-(CN1-RX-)") (class "Default")
      (node (ref "CN1") (pin "6") (pinfunction "RX-_6") (pintype "passive"))
      (node (ref "T3") (pin "9") (pinfunction "rx-_9") (pintype "passive"))
    )
    (net (code "29") (name "Net-(CN1-TX+)") (class "Default")
      (node (ref "CN1") (pin "1") (pinfunction "TX+_1") (pintype "passive"))
      (node (ref "T3") (pin "16") (pinfunction "tx1+_16") (pintype "passive"))
    )
    (net (code "30") (name "Net-(CN1-TX-)") (class "Default")
      (node (ref "CN1") (pin "2") (pinfunction "TX-_2") (pintype "passive"))
      (node (ref "T3") (pin "14") (pinfunction "tx1-_14") (pintype "passive"))
    )
    (net (code "31") (name "Net-(D1-A)") (class "Default")
      (node (ref "C13") (pin "1") (pinfunction "1_1") (pintype "passive"))
      (node (ref "C82") (pin "2") (pinfunction "2_2") (pintype "passive"))
      (node (ref "C9") (pin "2") (pinfunction "2_2") (pintype "passive"))
      (node (ref "C91") (pin "2") (pinfunction "2_2") (pintype "passive"))
      (node (ref "C92") (pin "1") (pinfunction "1_1") (pintype "passive"))
      (node (ref "D1") (pin "1") (pinfunction "A_1") (pintype "passive"))
      (node (ref "D7") (pin "1") (pinfunction "A_1") (pintype "passive"))
      (node (ref "R12") (pin "2") (pinfunction "2_2") (pintype "passive"))
      (node (ref "R129") (pin "1") (pinfunction "1_1") (pintype "passive"))
      (node (ref "R131") (pin "1") (pinfunction "1_1") (pintype "passive"))
      (node (ref "U8") (pin "8") (pinfunction "VSS_8") (pintype "passive"))
      (node (ref "U8") (pin "EP") (pinfunction "EPAD_EP") (pintype "passive"))
    )
    (net (code "32") (name "Net-(D1-K)") (class "Default")
      (node (ref "C1") (pin "2") (pinfunction "2_2") (pintype "passive"))
      (node (ref "C2") (pin "2") (pinfunction "2_2") (pintype "passive"))
      (node (ref "C6") (pin "2") (pinfunction "2_2") (pintype "passive"))
      (node (ref "C8") (pin "2") (pinfunction "2_2") (pintype "passive"))
      (node (ref "C9") (pin "1") (pinfunction "1_1") (pintype "passive"))
      (node (ref "D1") (pin "2") (pinfunction "K_2") (pintype "passive"))
      (node (ref "L1") (pin "2") (pinfunction "2_2") (pintype "passive"))
      (node (ref "R13") (pin "2") (pinfunction "2_2") (pintype "passive"))
      (node (ref "R32") (pin "2") (pinfunction "2_2") (pintype "passive"))
    )
    (net (code "33") (name "Net-(D2-A)") (class "Default")
      (node (ref "D2") (pin "1") (pinfunction "A_1") (pintype "passive"))
      (node (ref "R5") (pin "1") (pinfunction "1_1") (pintype "passive"))
    )
    (net (code "34") (name "Net-(D2-K)") (class "Default")
      (node (ref "C60") (pin "2") (pinfunction "2_2") (pintype "passive"))
      (node (ref "C61") (pin "2") (pinfunction "2_2") (pintype "passive"))
      (node (ref "D2") (pin "2") (pinfunction "K_2") (pintype "passive"))
      (node (ref "R10") (pin "2") (pinfunction "2_2") (pintype "passive"))
      (node (ref "U8") (pin "11") (pinfunction "VCC_11") (pintype "passive"))
    )
    (net (code "35") (name "Net-(D3-K)") (class "Default")
      (node (ref "C11") (pin "2") (pinfunction "2_2") (pintype "passive"))
      (node (ref "C12") (pin "2") (pinfunction "2_2") (pintype "passive"))
      (node (ref "D3") (pin "2") (pinfunction "K_2") (pintype "passive"))
      (node (ref "R4") (pin "1") (pinfunction "1_1") (pintype "passive"))
    )
    (net (code "36") (name "Net-(D4-AC_IN_1)") (class "Default")
      (node (ref "D4") (pin "1") (pinfunction "AC_IN_1_1") (pintype "passive"))
      (node (ref "R28") (pin "2") (pinfunction "2_2") (pintype "passive"))
      (node (ref "T3") (pin "15") (pinfunction "txct_15") (pintype "passive"))
    )
    (net (code "37") (name "Net-(D4-AC_IN_2)") (class "Default")
      (node (ref "D4") (pin "2") (pinfunction "AC_IN_2_2") (pintype "passive"))
      (node (ref "R15") (pin "2") (pinfunction "2_2") (pintype "passive"))
      (node (ref "T3") (pin "10") (pinfunction "rxct_10") (pintype "passive"))
    )
    (net (code "38") (name "Net-(D4-DC_OUT_MINUS)") (class "Default")
      (node (ref "C23") (pin "1") (pinfunction "1_1") (pintype "passive"))
      (node (ref "D4") (pin "4") (pinfunction "DC_OUT_MINUS_4") (pintype "passive"))
      (node (ref "D5") (pin "4") (pinfunction "DC_OUT_MINUS_4") (pintype "passive"))
      (node (ref "R12") (pin "1") (pinfunction "1_1") (pintype "passive"))
    )
    (net (code "39") (name "Net-(D4-DC_OUT_PLUS)") (class "Default")
      (node (ref "C23") (pin "2") (pinfunction "2_2") (pintype "passive"))
      (node (ref "D4") (pin "3") (pinfunction "DC_OUT_PLUS_3") (pintype "passive"))
      (node (ref "D5") (pin "3") (pinfunction "DC_OUT_PLUS_3") (pintype "passive"))
      (node (ref "R13") (pin "1") (pinfunction "1_1") (pintype "passive"))
    )
    (net (code "40") (name "Net-(D5-AC_IN_1)") (class "Default")
      (node (ref "CN1") (pin "7") (pinfunction "NC_7") (pintype "passive"))
      (node (ref "CN1") (pin "8") (pinfunction "NC_8") (pintype "passive"))
      (node (ref "D5") (pin "1") (pinfunction "AC_IN_1_1") (pintype "passive"))
      (node (ref "R11") (pin "2") (pinfunction "2_2") (pintype "passive"))
    )
    (net (code "41") (name "Net-(D5-AC_IN_2)") (class "Default")
      (node (ref "CN1") (pin "4") (pinfunction "NC_4") (pintype "passive"))
      (node (ref "CN1") (pin "5") (pinfunction "NC_5") (pintype "passive"))
      (node (ref "D5") (pin "2") (pinfunction "AC_IN_2_2") (pintype "passive"))
      (node (ref "R27") (pin "2") (pinfunction "2_2") (pintype "passive"))
    )
    (net (code "42") (name "Net-(D6-A)") (class "Default")
      (node (ref "D6") (pin "1") (pinfunction "A_1") (pintype "passive"))
      (node (ref "R71") (pin "2") (pinfunction "2_2") (pintype "passive"))
      (node (ref "R87") (pin "2") (pinfunction "2_2") (pintype "passive"))
      (node (ref "T4") (pin "1") (pinfunction "G_1") (pintype "passive"))
    )
    (net (code "43") (name "Net-(D6-K)") (class "Default")
      (node (ref "D6") (pin "2") (pinfunction "K_2") (pintype "passive"))
      (node (ref "R72") (pin "1") (pinfunction "1_1") (pintype "passive"))
    )
    (net (code "44") (name "Net-(T3-rct)") (class "Default")
      (node (ref "R82") (pin "1") (pinfunction "1_1") (pintype "passive"))
      (node (ref "T3") (pin "7") (pinfunction "rct_7") (pintype "passive"))
    )
    (net (code "45") (name "Net-(T4-S)") (class "Default")
      (node (ref "C58") (pin "2") (pinfunction "2_2") (pintype "passive"))
      (node (ref "R85") (pin "2") (pinfunction "2_2") (pintype "passive"))
      (node (ref "R92") (pin "1") (pinfunction "1_1") (pintype "passive"))
      (node (ref "R92") (pin "2") (pinfunction "2_2") (pintype "passive"))
      (node (ref "T4") (pin "3") (pinfunction "S_3") (pintype "passive"))
      (node (ref "U8") (pin "13") (pinfunction "CS_13") (pintype "passive"))
    )
    (net (code "46") (name "Net-(U4-Anode)") (class "Default")
      (node (ref "C26") (pin "1") (pinfunction "1_1") (pintype "passive"))
      (node (ref "R34") (pin "1") (pinfunction "1_1") (pintype "passive"))
      (node (ref "U4") (pin "1") (pinfunction "Anode_1") (pintype "passive"))
    )
    (net (code "47") (name "Net-(U4-B)") (class "Default")
      (node (ref "C34") (pin "1") (pinfunction "1_1") (pintype "passive"))
      (node (ref "R68") (pin "2") (pinfunction "2_2") (pintype "passive"))
      (node (ref "U4") (pin "2") (pinfunction "B_2") (pintype "passive"))
    )
    (net (code "48") (name "Net-(U4-Collector)") (class "Default")
      (node (ref "R57") (pin "2") (pinfunction "2_2") (pintype "passive"))
      (node (ref "U4") (pin "4") (pinfunction "Collector_4") (pintype "passive"))
      (node (ref "U8") (pin "14") (pinfunction "COMP_14") (pintype "passive"))
    )
    (net (code "49") (name "Net-(U5-K)") (class "Default")
      (node (ref "C28") (pin "1") (pinfunction "1_1") (pintype "passive"))
      (node (ref "C32") (pin "1") (pinfunction "1_1") (pintype "passive"))
      (node (ref "C34") (pin "2") (pinfunction "2_2") (pintype "passive"))
      (node (ref "R68") (pin "1") (pinfunction "1_1") (pintype "passive"))
      (node (ref "U5") (pin "3") (pinfunction "K_3") (pintype "passive"))
    )
    (net (code "50") (name "Net-(U5-REF)") (class "Default")
      (node (ref "C28") (pin "2") (pinfunction "2_2") (pintype "passive"))
      (node (ref "R33") (pin "1") (pinfunction "1_1") (pintype "passive"))
      (node (ref "R35") (pin "1") (pinfunction "1_1") (pintype "passive"))
      (node (ref "R52") (pin "2") (pinfunction "2_2") (pintype "passive"))
      (node (ref "R58") (pin "1") (pinfunction "1_1") (pintype "passive"))
      (node (ref "U5") (pin "4") (pinfunction "REF_4") (pintype "passive"))
    )
    (net (code "51") (name "Net-(U8-AUXII)") (class "Default")
      (node (ref "C93") (pin "1") (pinfunction "1_1") (pintype "passive"))
      (node (ref "U8") (pin "3") (pinfunction "AUXII_3") (pintype "passive"))
    )
    (net (code "52") (name "Net-(U8-AUXI_IRL)") (class "Default")
      (node (ref "C92") (pin "2") (pinfunction "2_2") (pintype "passive"))
      (node (ref "U8") (pin "6") (pinfunction "AUXI_IRL_6") (pintype "passive"))
    )
    (net (code "53") (name "Net-(U8-DCCL)") (class "Default")
      (node (ref "R131") (pin "2") (pinfunction "2_2") (pintype "passive"))
      (node (ref "U8") (pin "7") (pinfunction "DCCL_7") (pintype "passive"))
    )
    (net (code "54") (name "Net-(U8-GD)") (class "Default")
      (node (ref "R71") (pin "1") (pinfunction "1_1") (pintype "passive"))
      (node (ref "R72") (pin "2") (pinfunction "2_2") (pintype "passive"))
      (node (ref "U8") (pin "10") (pinfunction "GD_10") (pintype "passive"))
    )
    (net (code "55") (name "Net-(U8-RCLASS)") (class "Default")
      (node (ref "R129") (pin "2") (pinfunction "2_2") (pintype "passive"))
      (node (ref "U8") (pin "5") (pinfunction "RCLASS_5") (pintype "passive"))
    )
    (net (code "56") (name "Net-(U8-RT)") (class "Default")
      (node (ref "R118") (pin "1") (pinfunction "1_1") (pintype "passive"))
      (node (ref "U8") (pin "1") (pinfunction "RT_1") (pintype "passive"))
    )
    (net (code "57") (name "Net-(U8-SS)") (class "Default")
      (node (ref "C90") (pin "1") (pinfunction "1_1") (pintype "passive"))
      (node (ref "U8") (pin "2") (pinfunction "SS_2") (pintype "passive"))
    )
    (net (code "58") (name "Net-(U8-VIN)") (class "Default")
      (node (ref "C91") (pin "1") (pinfunction "1_1") (pintype "passive"))
      (node (ref "R32") (pin "1") (pinfunction "1_1") (pintype "passive"))
      (node (ref "U8") (pin "4") (pinfunction "VIN_4") (pintype "passive"))
    )
    (net (code "59") (name "Net-(U8-nPGD)") (class "Default")
      (node (ref "C59") (pin "2") (pinfunction "2_2") (pintype "passive"))
      (node (ref "R10") (pin "1") (pinfunction "1_1") (pintype "passive"))
      (node (ref "U8") (pin "12") (pinfunction "nPGD_12") (pintype "passive"))
    )
    (net (code "60") (name "VDD_ETH") (class "Default")
      (node (ref "C51") (pin "2") (pinfunction "2_2") (pintype "passive"))
      (node (ref "R82") (pin "2") (pinfunction "2_2") (pintype "passive"))
      (node (ref "T3") (pin "2") (pinfunction "tct_2") (pintype "passive"))
    )
    (net (code "61") (name "unconnected-(U5-NC-Pad1)") (class "Default")
      (node (ref "U5") (pin "1") (pinfunction "NC_1") (pintype "passive+no_connect"))
    )
    (net (code "62") (name "unconnected-(U5-NC-Pad2)") (class "Default")
      (node (ref "U5") (pin "2") (pinfunction "NC_2") (pintype "passive+no_connect"))
    )
  )
)
